# T15_PRI_SYS_V1_2.net
KiCad netlist of a schematic drawn in EAGLE
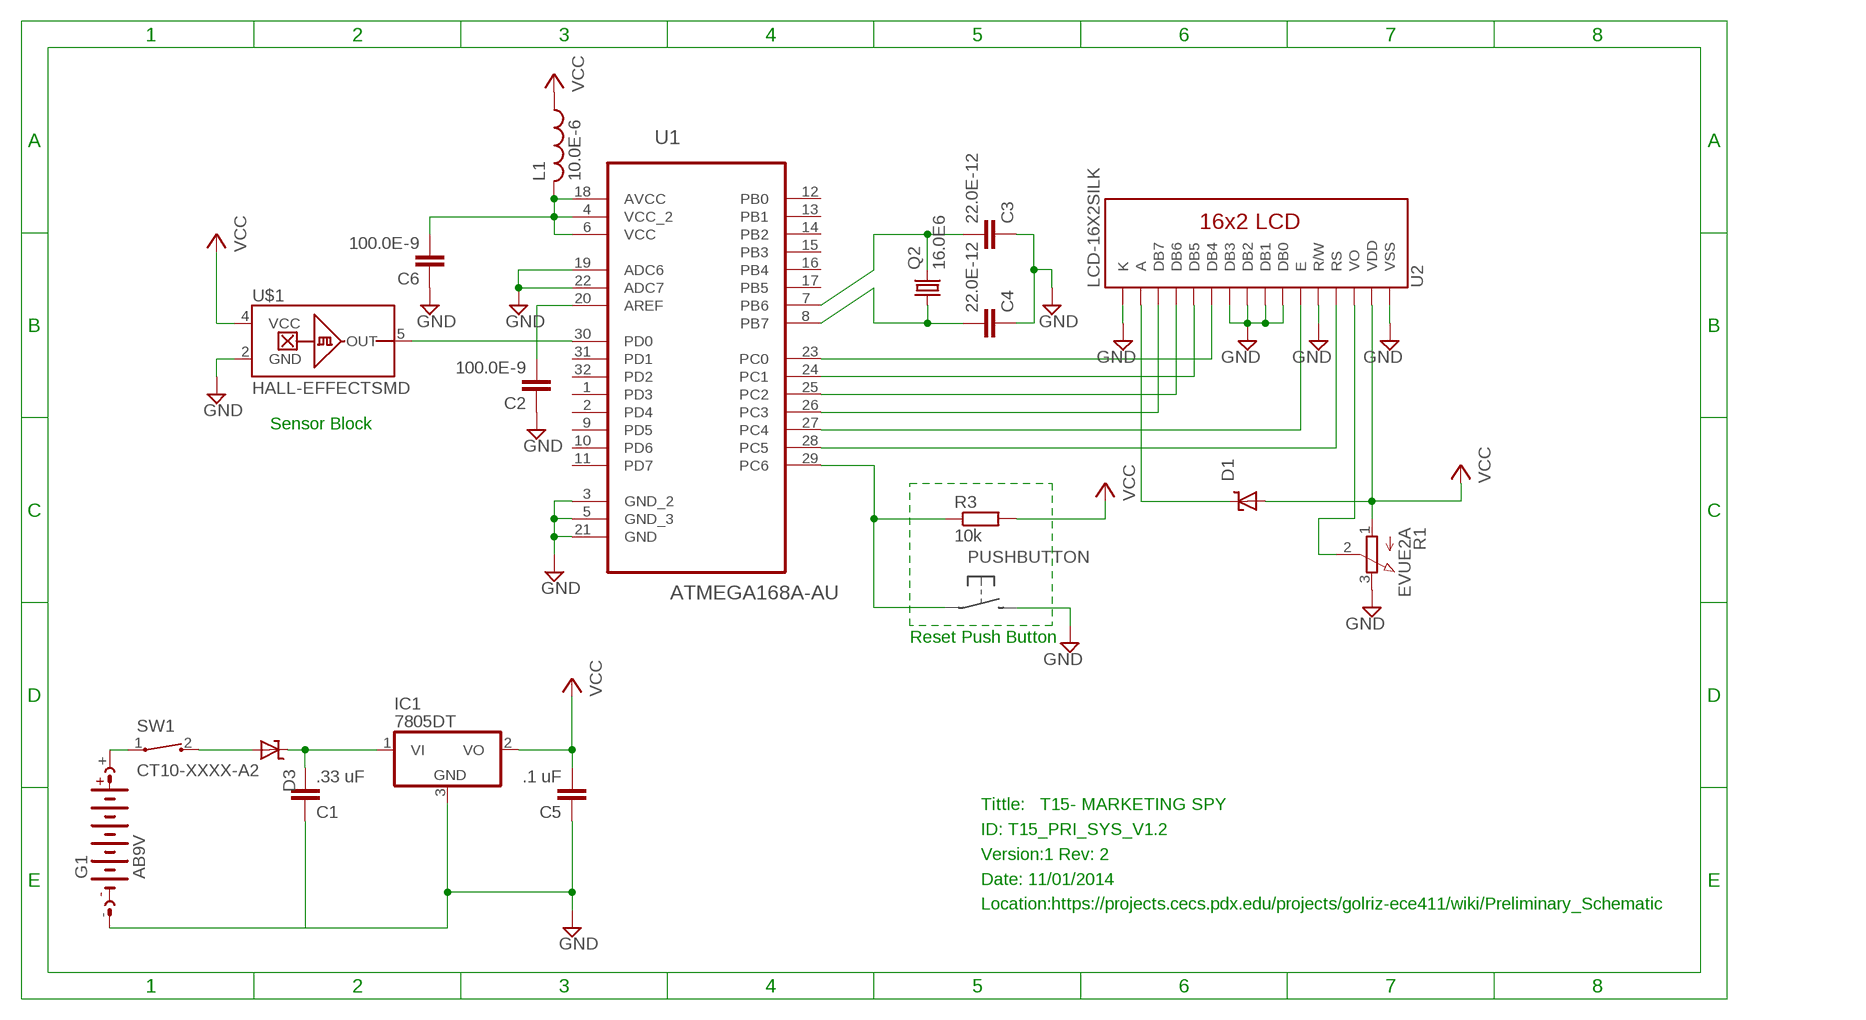
[diagram p0: schematic, sheet 1]

(export (version "E")
  (design (tool "Eeschema 10.0.6"))
  (components
    (comp (ref "C1")
      (value ".33 uF")
      (footprint "eagle-import:C025-024X044")
      (libsource (lib "eagle-import") (part "C-EU025-024X044"))
    )
    (comp (ref "C2")
      (value "100.0E-9")
      (footprint "eagle-import:C025-024X044")
      (libsource (lib "eagle-import") (part "C-EU025-024X044"))
    )
    (comp (ref "C3")
      (value "22.0E-12")
      (footprint "eagle-import:C025-024X044")
      (libsource (lib "eagle-import") (part "C-EU025-024X044"))
    )
    (comp (ref "C4")
      (value "22.0E-12")
      (footprint "eagle-import:C025-024X044")
      (libsource (lib "eagle-import") (part "C-EU025-024X044"))
    )
    (comp (ref "C5")
      (value ".1 uF")
      (footprint "eagle-import:C025-024X044")
      (libsource (lib "eagle-import") (part "C-EU025-024X044"))
    )
    (comp (ref "C6")
      (value "100.0E-9")
      (footprint "eagle-import:C025-024X044")
      (libsource (lib "eagle-import") (part "C-EU025-024X044"))
    )
    (comp (ref "D1")
      (value "SUPPRESSOR-SMBJ")
      (footprint "eagle-import:SMBJ")
      (libsource (lib "eagle-import") (part "SUPPRESSOR-SMBJ"))
    )
    (comp (ref "D3")
      (value "SUPPRESSOR-SMBJ")
      (footprint "eagle-import:SMBJ")
      (libsource (lib "eagle-import") (part "SUPPRESSOR-SMBJ"))
    )
    (comp (ref "G1")
      (value "AB9V")
      (footprint "eagle-import:AB9V")
      (libsource (lib "eagle-import") (part "AB9V"))
    )
    (comp (ref "IC1")
      (value "7805DT")
      (footprint "eagle-import:TO252")
      (libsource (lib "eagle-import") (part "78DT05"))
    )
    (comp (ref "L1")
      (value "10.0E-6")
      (footprint "eagle-import:0204_5")
      (libsource (lib "eagle-import") (part "L-US0204/5"))
    )
    (comp (ref "Q2")
      (value "16.0E6")
      (footprint "eagle-import:HC49_S")
      (libsource (lib "eagle-import") (part "CRYSTALHC49S"))
    )
    (comp (ref "R1")
      (value "EVUE2A")
      (footprint "eagle-import:EVUE")
      (libsource (lib "eagle-import") (part "EVUE2A"))
    )
    (comp (ref "R3")
      (value "10k")
      (footprint "eagle-import:0204_5")
      (libsource (lib "eagle-import") (part "R-EU_0204/5"))
    )
    (comp (ref "SW1")
      (value "CT10-XXXX-A2")
      (footprint "eagle-import:CT10-XXXX-A2")
      (libsource (lib "eagle-import") (part "CT10-XXXX-A2"))
    )
    (comp (ref "U$1")
      (value "HALL-EFFECTSMD")
      (footprint "eagle-import:SC70")
      (libsource (lib "eagle-import") (part "HALL-EFFECTSMD"))
    )
    (comp (ref "U1")
      (value "ATMEGA168A-AU")
      (footprint "eagle-import:QFP80P900X900X120-32N")
      (libsource (lib "eagle-import") (part "ATMEGA168A-AU"))
    )
    (comp (ref "U2")
      (value "LCD-16X2SILK")
      (footprint "eagle-import:LCD-16X2")
      (libsource (lib "eagle-import") (part "LCD-16X2SILK"))
    )
  )
  (nets
    (net (code "1") (name "GND") (class "Default")
      (node (ref "C1") (pin "1") (pinfunction "1_1") (pintype "passive"))
      (node (ref "C2") (pin "1") (pinfunction "1_1") (pintype "passive"))
      (node (ref "C3") (pin "1") (pinfunction "1_1") (pintype "passive"))
      (node (ref "C4") (pin "1") (pinfunction "1_1") (pintype "passive"))
      (node (ref "C5") (pin "1") (pinfunction "1_1") (pintype "passive"))
      (node (ref "C6") (pin "1") (pinfunction "1_1") (pintype "passive"))
      (node (ref "G1") (pin "-") (pinfunction "-_-") (pintype "passive"))
      (node (ref "IC1") (pin "3") (pinfunction "GND_3") (pintype "passive"))
      (node (ref "R1") (pin "3") (pinfunction "E_3") (pintype "passive"))
      (node (ref "U$1") (pin "2") (pinfunction "GND_2") (pintype "bidirectional"))
      (node (ref "U1") (pin "19") (pinfunction "ADC6_19") (pintype "input"))
      (node (ref "U1") (pin "21") (pinfunction "GND_21") (pintype "passive"))
      (node (ref "U1") (pin "22") (pinfunction "ADC7_22") (pintype "input"))
      (node (ref "U1") (pin "3") (pinfunction "GND_2_3") (pintype "passive"))
      (node (ref "U1") (pin "5") (pinfunction "GND_3_5") (pintype "passive"))
      (node (ref "U2") (pin "1") (pinfunction "VSS_1") (pintype "power_in"))
      (node (ref "U2") (pin "10") (pinfunction "DB3_10") (pintype "bidirectional"))
      (node (ref "U2") (pin "16") (pinfunction "K_16") (pintype "power_in"))
      (node (ref "U2") (pin "5") (pinfunction "R/W_5") (pintype "input"))
      (node (ref "U2") (pin "7") (pinfunction "DB0_7") (pintype "bidirectional"))
      (node (ref "U2") (pin "8") (pinfunction "DB1_8") (pintype "bidirectional"))
      (node (ref "U2") (pin "9") (pinfunction "DB2_9") (pintype "bidirectional"))
    )
    (net (code "2") (name "Net-(D3-PadA)") (class "Default")
      (node (ref "D3") (pin "A") (pinfunction "A_A") (pintype "passive"))
      (node (ref "SW1") (pin "2") (pinfunction "2_2") (pintype "passive"))
    )
    (net (code "3") (name "Net-(G1-Pad+)") (class "Default")
      (node (ref "G1") (pin "+") (pinfunction "+_+") (pintype "passive"))
      (node (ref "SW1") (pin "1") (pinfunction "1_1") (pintype "passive"))
    )
    (net (code "4") (name "Net-(IC1-VI)") (class "Default")
      (node (ref "C1") (pin "2") (pinfunction "2_2") (pintype "passive"))
      (node (ref "D3") (pin "C") (pinfunction "C_C") (pintype "passive"))
      (node (ref "IC1") (pin "1") (pinfunction "VI_1") (pintype "input"))
    )
    (net (code "5") (name "Net-(R1-S)") (class "Default")
      (node (ref "R1") (pin "2") (pinfunction "S_2") (pintype "passive"))
      (node (ref "U2") (pin "3") (pinfunction "VO_3") (pintype "bidirectional"))
    )
    (net (code "6") (name "Net-(U$1-OUT)") (class "Default")
      (node (ref "U$1") (pin "5") (pinfunction "OUT_5") (pintype "bidirectional"))
      (node (ref "U1") (pin "30") (pinfunction "PD0_30") (pintype "bidirectional"))
    )
    (net (code "7") (name "Net-(U1-AREF)") (class "Default")
      (node (ref "C2") (pin "2") (pinfunction "2_2") (pintype "passive"))
      (node (ref "U1") (pin "20") (pinfunction "AREF_20") (pintype "input"))
    )
    (net (code "8") (name "Net-(U1-AVCC)") (class "Default")
      (node (ref "C6") (pin "2") (pinfunction "2_2") (pintype "passive"))
      (node (ref "L1") (pin "2") (pinfunction "2_2") (pintype "passive"))
      (node (ref "U1") (pin "18") (pinfunction "AVCC_18") (pintype "power_in"))
      (node (ref "U1") (pin "4") (pinfunction "VCC_2_4") (pintype "power_in"))
      (node (ref "U1") (pin "6") (pinfunction "VCC_6") (pintype "power_in"))
    )
    (net (code "9") (name "Net-(U1-PB6)") (class "Default")
      (node (ref "C3") (pin "2") (pinfunction "2_2") (pintype "passive"))
      (node (ref "Q2") (pin "2") (pinfunction "2_2") (pintype "passive"))
      (node (ref "U1") (pin "7") (pinfunction "PB6_7") (pintype "bidirectional"))
    )
    (net (code "10") (name "Net-(U1-PB7)") (class "Default")
      (node (ref "C4") (pin "2") (pinfunction "2_2") (pintype "passive"))
      (node (ref "Q2") (pin "1") (pinfunction "1_1") (pintype "passive"))
      (node (ref "U1") (pin "8") (pinfunction "PB7_8") (pintype "bidirectional"))
    )
    (net (code "11") (name "Net-(U1-PC0)") (class "Default")
      (node (ref "U1") (pin "23") (pinfunction "PC0_23") (pintype "bidirectional"))
      (node (ref "U2") (pin "11") (pinfunction "DB4_11") (pintype "bidirectional"))
    )
    (net (code "12") (name "Net-(U1-PC1)") (class "Default")
      (node (ref "U1") (pin "24") (pinfunction "PC1_24") (pintype "bidirectional"))
      (node (ref "U2") (pin "12") (pinfunction "DB5_12") (pintype "bidirectional"))
    )
    (net (code "13") (name "Net-(U1-PC2)") (class "Default")
      (node (ref "U1") (pin "25") (pinfunction "PC2_25") (pintype "bidirectional"))
      (node (ref "U2") (pin "13") (pinfunction "DB6_13") (pintype "bidirectional"))
    )
    (net (code "14") (name "Net-(U1-PC3)") (class "Default")
      (node (ref "U1") (pin "26") (pinfunction "PC3_26") (pintype "bidirectional"))
      (node (ref "U2") (pin "14") (pinfunction "DB7_14") (pintype "bidirectional"))
    )
    (net (code "15") (name "Net-(U1-PC4)") (class "Default")
      (node (ref "U1") (pin "27") (pinfunction "PC4_27") (pintype "bidirectional"))
      (node (ref "U2") (pin "6") (pinfunction "E_6") (pintype "input"))
    )
    (net (code "16") (name "Net-(U1-PC5)") (class "Default")
      (node (ref "U1") (pin "28") (pinfunction "PC5_28") (pintype "bidirectional"))
      (node (ref "U2") (pin "4") (pinfunction "RS_4") (pintype "input"))
    )
    (net (code "17") (name "Net-(U1-PC6)") (class "Default")
      (node (ref "R3") (pin "1") (pinfunction "1_1") (pintype "passive"))
      (node (ref "U1") (pin "29") (pinfunction "PC6_29") (pintype "bidirectional"))
    )
    (net (code "18") (name "Net-(U2-A)") (class "Default")
      (node (ref "D1") (pin "C") (pinfunction "C_C") (pintype "passive"))
      (node (ref "U2") (pin "15") (pinfunction "A_15") (pintype "power_in"))
    )
    (net (code "19") (name "VCC") (class "Default")
      (node (ref "C5") (pin "2") (pinfunction "2_2") (pintype "passive"))
      (node (ref "D1") (pin "A") (pinfunction "A_A") (pintype "passive"))
      (node (ref "IC1") (pin "2") (pinfunction "VO_2") (pintype "passive"))
      (node (ref "L1") (pin "1") (pinfunction "1_1") (pintype "passive"))
      (node (ref "R1") (pin "1") (pinfunction "A_1") (pintype "passive"))
      (node (ref "R3") (pin "2") (pinfunction "2_2") (pintype "passive"))
      (node (ref "U$1") (pin "4") (pinfunction "VCC_4") (pintype "bidirectional"))
      (node (ref "U2") (pin "2") (pinfunction "VDD_2") (pintype "power_in"))
    )
    (net (code "20") (name "unconnected-(U1-PB0-Pad12)") (class "Default")
      (node (ref "U1") (pin "12") (pinfunction "PB0_12") (pintype "bidirectional"))
    )
    (net (code "21") (name "unconnected-(U1-PB1-Pad13)") (class "Default")
      (node (ref "U1") (pin "13") (pinfunction "PB1_13") (pintype "bidirectional"))
    )
    (net (code "22") (name "unconnected-(U1-PB2-Pad14)") (class "Default")
      (node (ref "U1") (pin "14") (pinfunction "PB2_14") (pintype "bidirectional"))
    )
    (net (code "23") (name "unconnected-(U1-PB3-Pad15)") (class "Default")
      (node (ref "U1") (pin "15") (pinfunction "PB3_15") (pintype "bidirectional"))
    )
    (net (code "24") (name "unconnected-(U1-PB4-Pad16)") (class "Default")
      (node (ref "U1") (pin "16") (pinfunction "PB4_16") (pintype "bidirectional"))
    )
    (net (code "25") (name "unconnected-(U1-PB5-Pad17)") (class "Default")
      (node (ref "U1") (pin "17") (pinfunction "PB5_17") (pintype "bidirectional"))
    )
    (net (code "26") (name "unconnected-(U1-PD1-Pad31)") (class "Default")
      (node (ref "U1") (pin "31") (pinfunction "PD1_31") (pintype "bidirectional"))
    )
    (net (code "27") (name "unconnected-(U1-PD2-Pad32)") (class "Default")
      (node (ref "U1") (pin "32") (pinfunction "PD2_32") (pintype "bidirectional"))
    )
    (net (code "28") (name "unconnected-(U1-PD3-Pad1)") (class "Default")
      (node (ref "U1") (pin "1") (pinfunction "PD3_1") (pintype "bidirectional"))
    )
    (net (code "29") (name "unconnected-(U1-PD4-Pad2)") (class "Default")
      (node (ref "U1") (pin "2") (pinfunction "PD4_2") (pintype "bidirectional"))
    )
    (net (code "30") (name "unconnected-(U1-PD5-Pad9)") (class "Default")
      (node (ref "U1") (pin "9") (pinfunction "PD5_9") (pintype "bidirectional"))
    )
    (net (code "31") (name "unconnected-(U1-PD6-Pad10)") (class "Default")
      (node (ref "U1") (pin "10") (pinfunction "PD6_10") (pintype "bidirectional"))
    )
    (net (code "32") (name "unconnected-(U1-PD7-Pad11)") (class "Default")
      (node (ref "U1") (pin "11") (pinfunction "PD7_11") (pintype "bidirectional"))
    )
  )
)
